# Copperclad_CooperBuffer_Amp_V0-6.net
KiCad netlist of a schematic drawn in EAGLE
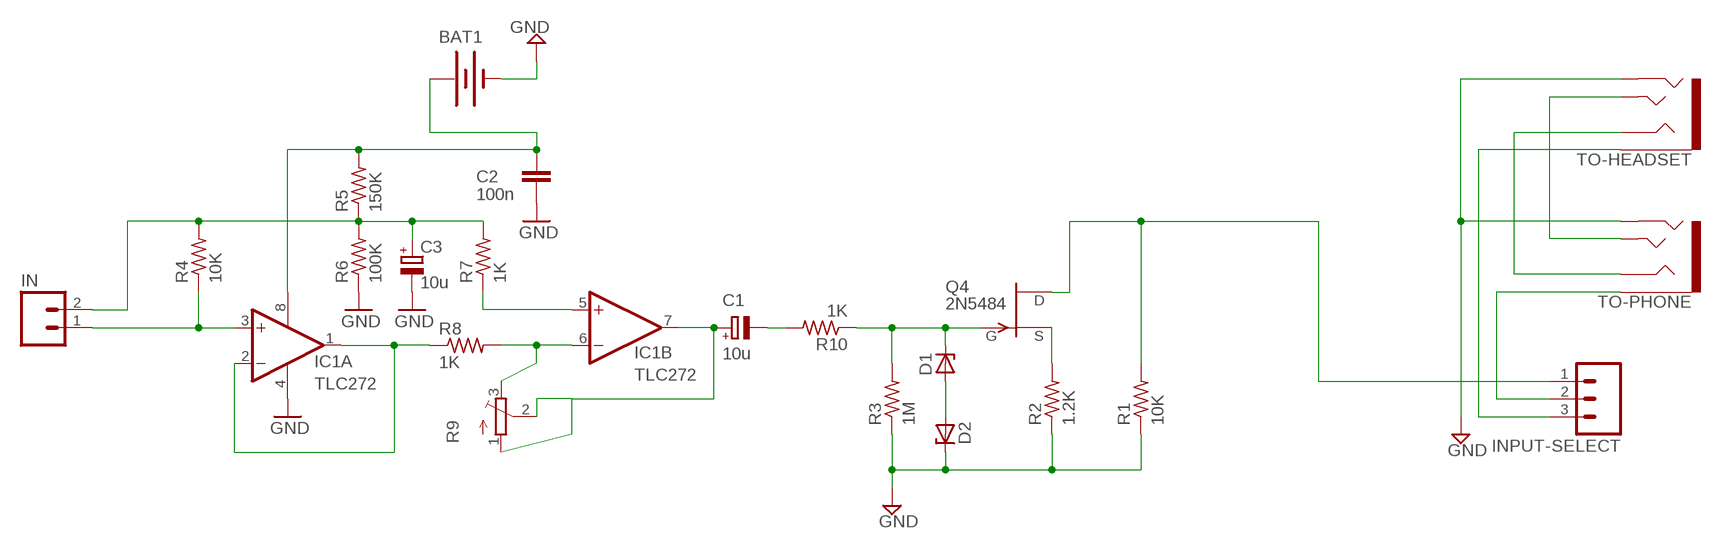
[diagram p0: schematic, sheet 1]

(export (version "E")
  (design (tool "Eeschema 10.0.6"))
  (components
    (comp (ref "BAT1")
      (value "BATTERYA23")
      (footprint "eagle-import:BATTERY-A23")
      (libsource (lib "eagle-import") (part "BATTERYA23"))
    )
    (comp (ref "C1")
      (value "10u")
      (footprint "eagle-import:E2,5-5")
      (libsource (lib "eagle-import") (part "CPOL-EUE2.5-5"))
    )
    (comp (ref "C2")
      (value "100n")
      (footprint "eagle-import:C025-025X050")
      (libsource (lib "eagle-import") (part "C-EU025-025X050"))
    )
    (comp (ref "C3")
      (value "10u")
      (footprint "eagle-import:E2,5-5")
      (libsource (lib "eagle-import") (part "CPOL-EUE2.5-5"))
    )
    (comp (ref "D1")
      (value "1N821")
      (footprint "eagle-import:DO35Z10")
      (libsource (lib "eagle-import") (part "1N821"))
    )
    (comp (ref "D2")
      (value "1N821")
      (footprint "eagle-import:DO35Z10")
      (libsource (lib "eagle-import") (part "1N821"))
    )
    (comp (ref "IC1")
      (value "TLC272")
      (footprint "eagle-import:DIL08")
      (libsource (lib "eagle-import") (part "TLC272P"))
    )
    (comp (ref "IN")
      (value "M02LOCK")
      (footprint "eagle-import:1X02_LOCK")
      (libsource (lib "eagle-import") (part "M02LOCK"))
    )
    (comp (ref "INPUT-SELECT")
      (value "M03LOCK")
      (footprint "eagle-import:1X03_LOCK")
      (libsource (lib "eagle-import") (part "M03LOCK"))
    )
    (comp (ref "Q4")
      (value "2N5484")
      (footprint "eagle-import:TO92-")
      (libsource (lib "eagle-import") (part "?5482N4"))
    )
    (comp (ref "R1")
      (value "10K")
      (footprint "eagle-import:0204V")
      (libsource (lib "eagle-import") (part "R-US_0204/2V"))
    )
    (comp (ref "R2")
      (value "1.2K")
      (footprint "eagle-import:0204V")
      (libsource (lib "eagle-import") (part "R-US_0204/2V"))
    )
    (comp (ref "R3")
      (value "1M")
      (footprint "eagle-import:0204V")
      (libsource (lib "eagle-import") (part "R-US_0204/2V"))
    )
    (comp (ref "R4")
      (value "10K")
      (footprint "eagle-import:0204V")
      (libsource (lib "eagle-import") (part "R-US_0204/2V"))
    )
    (comp (ref "R5")
      (value "150K")
      (footprint "eagle-import:0204V")
      (libsource (lib "eagle-import") (part "R-US_0204/2V"))
    )
    (comp (ref "R6")
      (value "100K")
      (footprint "eagle-import:0204V")
      (libsource (lib "eagle-import") (part "R-US_0204/2V"))
    )
    (comp (ref "R7")
      (value "1K")
      (footprint "eagle-import:0204V")
      (libsource (lib "eagle-import") (part "R-US_0204/2V"))
    )
    (comp (ref "R8")
      (value "1K")
      (footprint "eagle-import:0204V")
      (libsource (lib "eagle-import") (part "R-US_0204/2V"))
    )
    (comp (ref "R9")
      (value "TRIMPOT3386")
      (footprint "eagle-import:TRIM-3386")
      (libsource (lib "eagle-import") (part "TRIMPOT3386"))
    )
    (comp (ref "R10")
      (value "1K")
      (footprint "eagle-import:0204V")
      (libsource (lib "eagle-import") (part "R-US_0204/2V"))
    )
    (comp (ref "TO-HEADSET")
      (value "AUDIO-JACK3")
      (footprint "eagle-import:AUDIO-JACK-TRRS-SMD")
      (libsource (lib "eagle-import") (part "AUDIO-JACK3"))
    )
    (comp (ref "TO-PHONE")
      (value "AUDIO-JACK3")
      (footprint "eagle-import:AUDIO-JACK-TRRS-SMD")
      (libsource (lib "eagle-import") (part "AUDIO-JACK3"))
    )
  )
  (nets
    (net (code "1") (name "GND") (class "Default")
      (node (ref "BAT1") (pin "GND@1") (pinfunction "-_GND@1") (pintype "power_in"))
      (node (ref "C2") (pin "1") (pinfunction "1_1") (pintype "passive"))
      (node (ref "C3") (pin "-") (pinfunction "-_-") (pintype "passive"))
      (node (ref "D2") (pin "C") (pinfunction "C_C") (pintype "passive"))
      (node (ref "IC1") (pin "4") (pinfunction "V-_4") (pintype "power_in"))
      (node (ref "R1") (pin "1") (pinfunction "1_1") (pintype "passive"))
      (node (ref "R2") (pin "1") (pinfunction "1_1") (pintype "passive"))
      (node (ref "R3") (pin "1") (pinfunction "1_1") (pintype "passive"))
      (node (ref "R6") (pin "1") (pinfunction "1_1") (pintype "passive"))
      (node (ref "TO-HEADSET") (pin "RING2") (pinfunction "RING2_RING2") (pintype "bidirectional"))
      (node (ref "TO-PHONE") (pin "RING2") (pinfunction "RING2_RING2") (pintype "bidirectional"))
    )
    (net (code "2") (name "Net-(BAT1-+)") (class "Default")
      (node (ref "BAT1") (pin "PWR@1") (pinfunction "+_PWR@1") (pintype "power_in"))
      (node (ref "C2") (pin "2") (pinfunction "2_2") (pintype "passive"))
      (node (ref "IC1") (pin "8") (pinfunction "V+_8") (pintype "power_in"))
      (node (ref "R5") (pin "2") (pinfunction "2_2") (pintype "passive"))
    )
    (net (code "3") (name "Net-(C1-Pad-)") (class "Default")
      (node (ref "C1") (pin "-") (pinfunction "-_-") (pintype "passive"))
      (node (ref "R10") (pin "2") (pinfunction "2_2") (pintype "passive"))
    )
    (net (code "4") (name "Net-(C3-Pad+)") (class "Default")
      (node (ref "C3") (pin "+") (pinfunction "+_+") (pintype "passive"))
      (node (ref "IN") (pin "2") (pinfunction "2_2") (pintype "passive"))
      (node (ref "R4") (pin "2") (pinfunction "2_2") (pintype "passive"))
      (node (ref "R5") (pin "1") (pinfunction "1_1") (pintype "passive"))
      (node (ref "R6") (pin "2") (pinfunction "2_2") (pintype "passive"))
      (node (ref "R7") (pin "2") (pinfunction "2_2") (pintype "passive"))
    )
    (net (code "5") (name "Net-(D1-PadA)") (class "Default")
      (node (ref "D1") (pin "A") (pinfunction "A_A") (pintype "passive"))
      (node (ref "D2") (pin "A") (pinfunction "A_A") (pintype "passive"))
    )
    (net (code "6") (name "Net-(IC1A-+IN)") (class "Default")
      (node (ref "IC1") (pin "3") (pinfunction "+IN_3") (pintype "input"))
      (node (ref "IN") (pin "1") (pinfunction "1_1") (pintype "passive"))
      (node (ref "R4") (pin "1") (pinfunction "1_1") (pintype "passive"))
    )
    (net (code "7") (name "Net-(IC1A--IN)") (class "Default")
      (node (ref "IC1") (pin "1") (pinfunction "OUT_1") (pintype "output"))
      (node (ref "IC1") (pin "2") (pinfunction "-IN_2") (pintype "input"))
      (node (ref "R8") (pin "1") (pinfunction "1_1") (pintype "passive"))
    )
    (net (code "8") (name "Net-(IC1B-+IN)") (class "Default")
      (node (ref "IC1") (pin "5") (pinfunction "+IN_5") (pintype "input"))
      (node (ref "R7") (pin "1") (pinfunction "1_1") (pintype "passive"))
    )
    (net (code "9") (name "Net-(IC1B--IN)") (class "Default")
      (node (ref "IC1") (pin "6") (pinfunction "-IN_6") (pintype "input"))
      (node (ref "R8") (pin "2") (pinfunction "2_2") (pintype "passive"))
      (node (ref "R9") (pin "3") (pinfunction "E_3") (pintype "passive"))
    )
    (net (code "10") (name "Net-(IC1B-OUT)") (class "Default")
      (node (ref "C1") (pin "+") (pinfunction "+_+") (pintype "passive"))
      (node (ref "IC1") (pin "7") (pinfunction "OUT_7") (pintype "output"))
      (node (ref "R9") (pin "1") (pinfunction "A_1") (pintype "passive"))
      (node (ref "R9") (pin "2") (pinfunction "S_2") (pintype "passive"))
    )
    (net (code "11") (name "Net-(INPUT-SELECT-Pad2)") (class "Default")
      (node (ref "INPUT-SELECT") (pin "2") (pinfunction "2_2") (pintype "passive"))
      (node (ref "TO-PHONE") (pin "EARTH") (pinfunction "EARTH_EARTH") (pintype "bidirectional"))
    )
    (net (code "12") (name "Net-(INPUT-SELECT-Pad3)") (class "Default")
      (node (ref "INPUT-SELECT") (pin "3") (pinfunction "3_3") (pintype "passive"))
      (node (ref "TO-HEADSET") (pin "EARTH") (pinfunction "EARTH_EARTH") (pintype "bidirectional"))
    )
    (net (code "13") (name "Net-(Q4-D)") (class "Default")
      (node (ref "INPUT-SELECT") (pin "1") (pinfunction "1_1") (pintype "passive"))
      (node (ref "Q4") (pin "3") (pinfunction "D_3") (pintype "passive"))
      (node (ref "R1") (pin "2") (pinfunction "2_2") (pintype "passive"))
    )
    (net (code "14") (name "Net-(Q4-G)") (class "Default")
      (node (ref "D1") (pin "C") (pinfunction "C_C") (pintype "passive"))
      (node (ref "Q4") (pin "1") (pinfunction "G_1") (pintype "passive"))
      (node (ref "R10") (pin "1") (pinfunction "1_1") (pintype "passive"))
      (node (ref "R3") (pin "2") (pinfunction "2_2") (pintype "passive"))
    )
    (net (code "15") (name "Net-(Q4-S)") (class "Default")
      (node (ref "Q4") (pin "2") (pinfunction "S_2") (pintype "passive"))
      (node (ref "R2") (pin "2") (pinfunction "2_2") (pintype "passive"))
    )
    (net (code "16") (name "Net-(TO-HEADSET-PadRING1)") (class "Default")
      (node (ref "TO-HEADSET") (pin "RING1") (pinfunction "RING1_RING1") (pintype "bidirectional"))
      (node (ref "TO-PHONE") (pin "RING1") (pinfunction "RING1_RING1") (pintype "bidirectional"))
    )
    (net (code "17") (name "Net-(TO-HEADSET-PadTIP)") (class "Default")
      (node (ref "TO-HEADSET") (pin "TIP") (pinfunction "TIP_TIP") (pintype "bidirectional"))
      (node (ref "TO-PHONE") (pin "TIP") (pinfunction "TIP_TIP") (pintype "bidirectional"))
    )
  )
)
